# 24vacToIrRelayBoard-v1_2.net
KiCad netlist of a schematic drawn in EAGLE
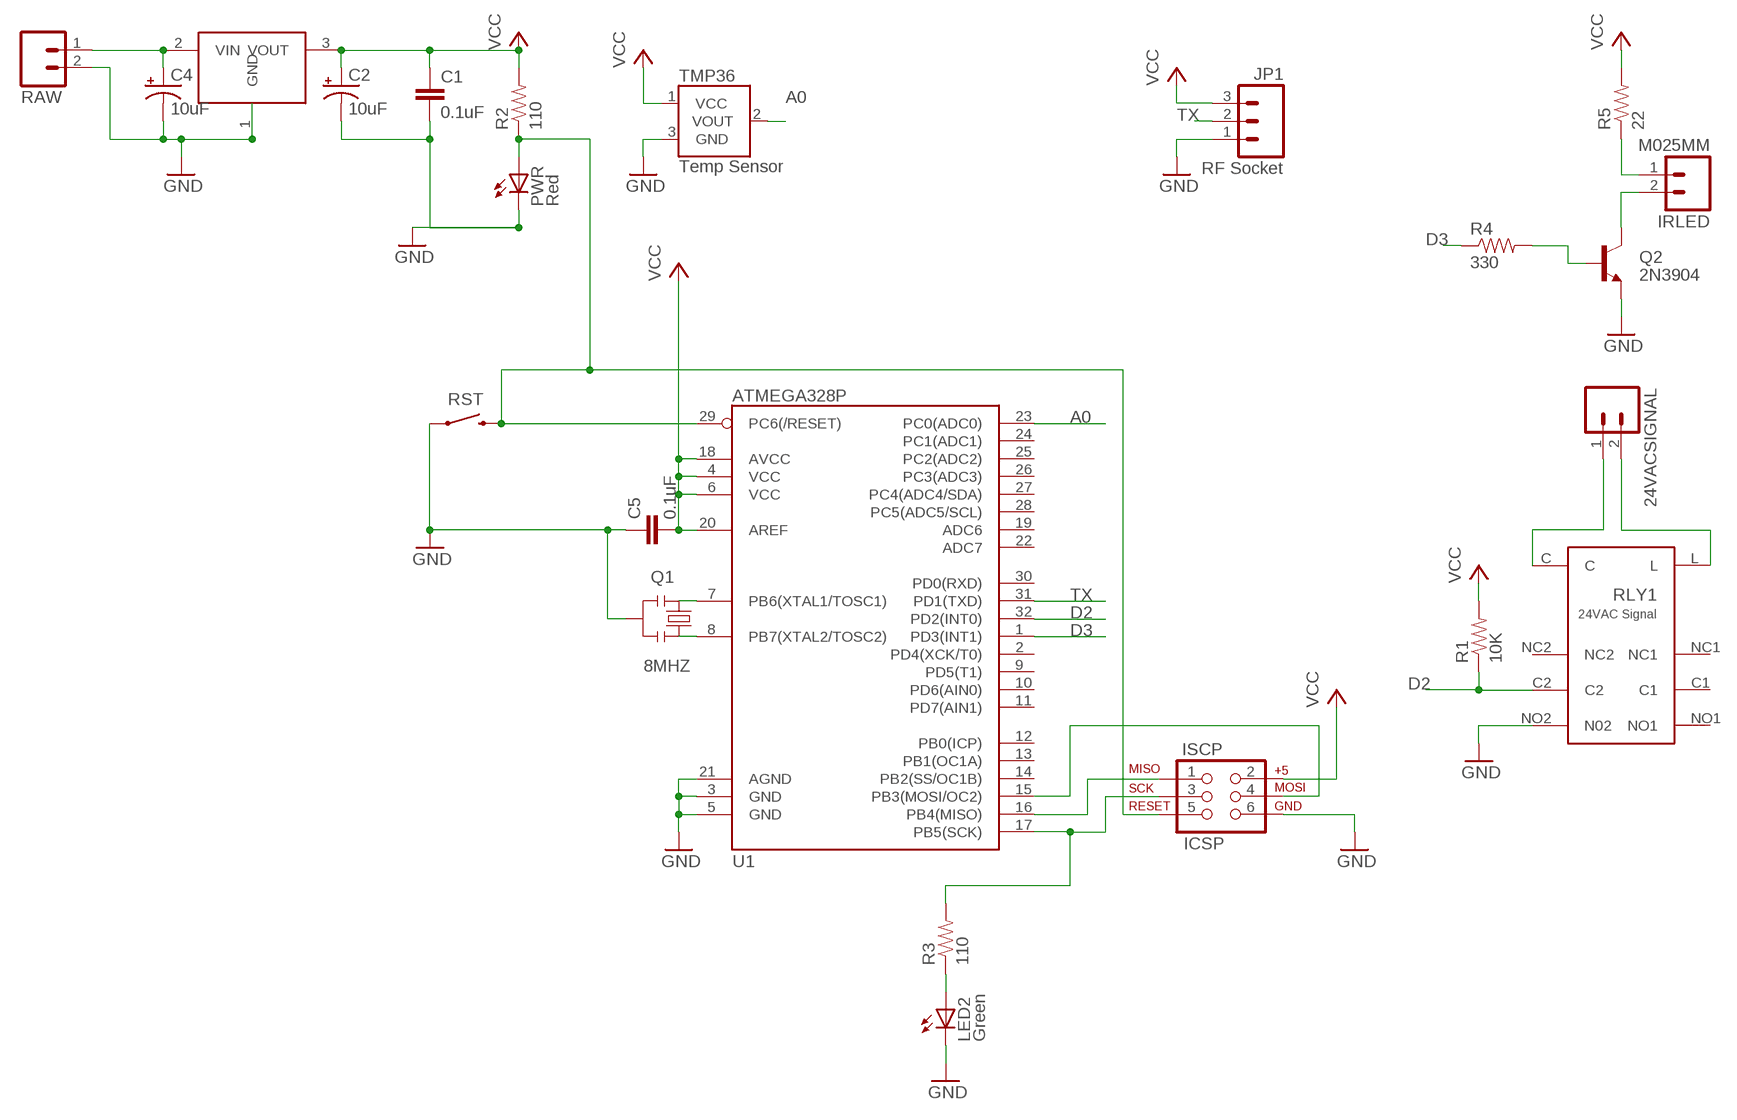
[diagram p0: schematic, sheet 1]

(export (version "E")
  (design (tool "Eeschema 10.0.6"))
  (components
    (comp (ref "24VACSIGNAL")
      (value "M025MM")
      (footprint "eagle-import:SCREWTERMINAL-5MM-2")
      (libsource (lib "eagle-import") (part "M025MM"))
    )
    (comp (ref "C1")
      (value "0.1uF")
      (footprint "eagle-import:0603-CAP")
      (libsource (lib "eagle-import") (part "0.1UF-25V-5%(0603)"))
    )
    (comp (ref "C2")
      (value "10uF")
      (footprint "eagle-import:EIA3216")
      (libsource (lib "eagle-import") (part "10UF-16V-10%(TANT)"))
    )
    (comp (ref "C4")
      (value "10uF")
      (footprint "eagle-import:EIA3216")
      (libsource (lib "eagle-import") (part "10UF-16V-10%(TANT)"))
    )
    (comp (ref "C5")
      (value "0.1uF")
      (footprint "eagle-import:0603-CAP")
      (libsource (lib "eagle-import") (part "0.1UF-25V-5%(0603)"))
    )
    (comp (ref "IRLED")
      (value "M025MM")
      (footprint "eagle-import:SCREWTERMINAL-5MM-2")
      (libsource (lib "eagle-import") (part "M025MM"))
    )
    (comp (ref "ISCP")
      (value "ICSP")
      (footprint "eagle-import:2X3-NS")
      (libsource (lib "eagle-import") (part "AVR_SPI_PRG_6NS"))
    )
    (comp (ref "JP1")
      (value "RF Socket")
      (footprint "eagle-import:1X03")
      (libsource (lib "eagle-import") (part "M03PTH"))
    )
    (comp (ref "LED2")
      (value "Green")
      (footprint "eagle-import:LED-0603")
      (libsource (lib "eagle-import") (part "LED0603"))
    )
    (comp (ref "PWR")
      (value "Red")
      (footprint "eagle-import:LED-0603")
      (libsource (lib "eagle-import") (part "LED0603"))
    )
    (comp (ref "Q1")
      (value "8MHZ")
      (footprint "eagle-import:RESONATOR-SMD")
      (libsource (lib "eagle-import") (part "RESONATOR8MHZ"))
    )
    (comp (ref "Q2")
      (value "2N3904")
      (footprint "eagle-import:SOT23-3")
      (libsource (lib "eagle-import") (part "TRANSISTOR_NPNSOT23-3"))
    )
    (comp (ref "R1")
      (value "10K")
      (footprint "eagle-import:0603-RES")
      (libsource (lib "eagle-import") (part "10KOHM1/10W1%(0603)0603"))
    )
    (comp (ref "R2")
      (value "110")
      (footprint "eagle-import:0603-RES")
      (libsource (lib "eagle-import") (part "10KOHM1/10W1%(0603)0603"))
    )
    (comp (ref "R3")
      (value "110")
      (footprint "eagle-import:0603-RES")
      (libsource (lib "eagle-import") (part "10KOHM1/10W1%(0603)0603"))
    )
    (comp (ref "R4")
      (value "330")
      (footprint "eagle-import:0603-RES")
      (libsource (lib "eagle-import") (part "10KOHM1/10W1%(0603)0603"))
    )
    (comp (ref "R5")
      (value "22")
      (footprint "eagle-import:0603-RES")
      (libsource (lib "eagle-import") (part "10KOHM1/10W1%(0603)0603"))
    )
    (comp (ref "RAW")
      (value "M025MM")
      (footprint "eagle-import:SCREWTERMINAL-5MM-2")
      (libsource (lib "eagle-import") (part "M025MM"))
    )
    (comp (ref "RLY1")
      (value "24VAC Signal")
      (footprint "eagle-import:976RELAY")
      (libsource (lib "eagle-import") (part "976XAX97H-24AA"))
    )
    (comp (ref "RST")
      (value "SWITCH-MOMENTARY-2PTH")
      (footprint "eagle-import:TACTILE-PTH")
      (libsource (lib "eagle-import") (part "SWITCH-MOMENTARY-2PTH"))
    )
    (comp (ref "TMP36")
      (value "Temp Sensor")
      (footprint "eagle-import:TO-92")
      (libsource (lib "eagle-import") (part "TMP36GT9"))
    )
    (comp (ref "U$1")
      (value "MCP1702")
      (footprint "eagle-import:TO92")
      (libsource (lib "eagle-import") (part "MCP1702"))
    )
    (comp (ref "U1")
      (value "ATMEGA328P")
      (footprint "eagle-import:TQFP32-08")
      (libsource (lib "eagle-import") (part "ATMEGA328_SMT"))
    )
  )
  (nets
    (net (code "1") (name "/A0") (class "Default")
      (node (ref "TMP36") (pin "2") (pinfunction "VOUT_2") (pintype "bidirectional"))
      (node (ref "U1") (pin "23") (pinfunction "PC0(ADC0)_23") (pintype "bidirectional"))
    )
    (net (code "2") (name "/D2") (class "Default")
      (node (ref "R1") (pin "1") (pinfunction "1_1") (pintype "passive"))
      (node (ref "RLY1") (pin "C2") (pinfunction "C2_C2") (pintype "bidirectional"))
      (node (ref "U1") (pin "32") (pinfunction "PD2(INT0)_32") (pintype "bidirectional"))
    )
    (net (code "3") (name "/D3") (class "Default")
      (node (ref "R4") (pin "1") (pinfunction "1_1") (pintype "passive"))
      (node (ref "U1") (pin "1") (pinfunction "PD3(INT1)_1") (pintype "bidirectional"))
    )
    (net (code "4") (name "/TX") (class "Default")
      (node (ref "JP1") (pin "2") (pinfunction "2_2") (pintype "passive"))
      (node (ref "U1") (pin "31") (pinfunction "PD1(TXD)_31") (pintype "bidirectional"))
    )
    (net (code "5") (name "GND") (class "Default")
      (node (ref "C1") (pin "2") (pinfunction "2_2") (pintype "passive"))
      (node (ref "C2") (pin "C") (pinfunction "-_C") (pintype "passive"))
      (node (ref "C4") (pin "C") (pinfunction "-_C") (pintype "passive"))
      (node (ref "C5") (pin "1") (pinfunction "1_1") (pintype "passive"))
      (node (ref "ISCP") (pin "6") (pinfunction "6_6") (pintype "passive"))
      (node (ref "JP1") (pin "1") (pinfunction "1_1") (pintype "passive"))
      (node (ref "LED2") (pin "C") (pinfunction "C_C") (pintype "passive"))
      (node (ref "PWR") (pin "C") (pinfunction "C_C") (pintype "passive"))
      (node (ref "Q1") (pin "2") (pinfunction "2_2") (pintype "passive"))
      (node (ref "Q2") (pin "2") (pinfunction "E_2") (pintype "passive"))
      (node (ref "RAW") (pin "2") (pinfunction "2_2") (pintype "passive"))
      (node (ref "RLY1") (pin "NO2") (pinfunction "N02_NO2") (pintype "bidirectional"))
      (node (ref "RST") (pin "1") (pinfunction "1_1") (pintype "passive"))
      (node (ref "TMP36") (pin "3") (pinfunction "GND_3") (pintype "bidirectional"))
      (node (ref "U$1") (pin "1") (pinfunction "GND_1") (pintype "bidirectional"))
      (node (ref "U1") (pin "21") (pinfunction "AGND_21") (pintype "bidirectional"))
      (node (ref "U1") (pin "3") (pinfunction "GND_3") (pintype "bidirectional"))
      (node (ref "U1") (pin "5") (pinfunction "GND_5") (pintype "bidirectional"))
    )
    (net (code "6") (name "Net-(24VACSIGNAL-Pad1)") (class "Default")
      (node (ref "24VACSIGNAL") (pin "1") (pinfunction "1_1") (pintype "passive"))
      (node (ref "RLY1") (pin "C") (pinfunction "C_C") (pintype "bidirectional"))
    )
    (net (code "7") (name "Net-(24VACSIGNAL-Pad2)") (class "Default")
      (node (ref "24VACSIGNAL") (pin "2") (pinfunction "2_2") (pintype "passive"))
      (node (ref "RLY1") (pin "L") (pinfunction "L_L") (pintype "bidirectional"))
    )
    (net (code "8") (name "Net-(C4-+)") (class "Default")
      (node (ref "C4") (pin "A") (pinfunction "+_A") (pintype "passive"))
      (node (ref "RAW") (pin "1") (pinfunction "1_1") (pintype "passive"))
      (node (ref "U$1") (pin "2") (pinfunction "VIN_2") (pintype "input"))
    )
    (net (code "9") (name "Net-(IRLED-Pad1)") (class "Default")
      (node (ref "IRLED") (pin "1") (pinfunction "1_1") (pintype "passive"))
      (node (ref "R5") (pin "1") (pinfunction "1_1") (pintype "passive"))
    )
    (net (code "10") (name "Net-(LED2-PadA)") (class "Default")
      (node (ref "LED2") (pin "A") (pinfunction "A_A") (pintype "passive"))
      (node (ref "R3") (pin "1") (pinfunction "1_1") (pintype "passive"))
    )
    (net (code "11") (name "Net-(Q2-B)") (class "Default")
      (node (ref "Q2") (pin "1") (pinfunction "B_1") (pintype "passive"))
      (node (ref "R4") (pin "2") (pinfunction "2_2") (pintype "passive"))
    )
    (net (code "12") (name "Net-(Q2-C)") (class "Default")
      (node (ref "IRLED") (pin "2") (pinfunction "2_2") (pintype "passive"))
      (node (ref "Q2") (pin "3") (pinfunction "C_3") (pintype "passive"))
    )
    (net (code "13") (name "Net-(RST-2)") (class "Default")
      (node (ref "ISCP") (pin "5") (pinfunction "5_5") (pintype "passive"))
      (node (ref "PWR") (pin "A") (pinfunction "A_A") (pintype "passive"))
      (node (ref "R2") (pin "1") (pinfunction "1_1") (pintype "passive"))
      (node (ref "RST") (pin "3") (pinfunction "2_3") (pintype "passive"))
      (node (ref "U1") (pin "29") (pinfunction "PC6(/RESET)_29") (pintype "bidirectional"))
    )
    (net (code "14") (name "Net-(U1-PB3(MOSI{slash}OC2))") (class "Default")
      (node (ref "ISCP") (pin "4") (pinfunction "4_4") (pintype "passive"))
      (node (ref "U1") (pin "15") (pinfunction "PB3(MOSI/OC2)_15") (pintype "bidirectional"))
    )
    (net (code "15") (name "Net-(U1-PB4(MISO))") (class "Default")
      (node (ref "ISCP") (pin "1") (pinfunction "1_1") (pintype "passive"))
      (node (ref "U1") (pin "16") (pinfunction "PB4(MISO)_16") (pintype "bidirectional"))
    )
    (net (code "16") (name "Net-(U1-PB5(SCK))") (class "Default")
      (node (ref "ISCP") (pin "3") (pinfunction "3_3") (pintype "passive"))
      (node (ref "R3") (pin "2") (pinfunction "2_2") (pintype "passive"))
      (node (ref "U1") (pin "17") (pinfunction "PB5(SCK)_17") (pintype "bidirectional"))
    )
    (net (code "17") (name "Net-(U1-PB6(XTAL1{slash}TOSC1))") (class "Default")
      (node (ref "Q1") (pin "1") (pinfunction "1_1") (pintype "passive"))
      (node (ref "U1") (pin "7") (pinfunction "PB6(XTAL1/TOSC1)_7") (pintype "bidirectional"))
    )
    (net (code "18") (name "Net-(U1-PB7(XTAL2{slash}TOSC2))") (class "Default")
      (node (ref "Q1") (pin "3") (pinfunction "3_3") (pintype "passive"))
      (node (ref "U1") (pin "8") (pinfunction "PB7(XTAL2/TOSC2)_8") (pintype "bidirectional"))
    )
    (net (code "19") (name "VCC") (class "Default")
      (node (ref "C1") (pin "1") (pinfunction "1_1") (pintype "passive"))
      (node (ref "C2") (pin "A") (pinfunction "+_A") (pintype "passive"))
      (node (ref "C5") (pin "2") (pinfunction "2_2") (pintype "passive"))
      (node (ref "ISCP") (pin "2") (pinfunction "2_2") (pintype "passive"))
      (node (ref "JP1") (pin "3") (pinfunction "3_3") (pintype "passive"))
      (node (ref "R1") (pin "2") (pinfunction "2_2") (pintype "passive"))
      (node (ref "R2") (pin "2") (pinfunction "2_2") (pintype "passive"))
      (node (ref "R5") (pin "2") (pinfunction "2_2") (pintype "passive"))
      (node (ref "TMP36") (pin "1") (pinfunction "VCC_1") (pintype "bidirectional"))
      (node (ref "U$1") (pin "3") (pinfunction "VOUT_3") (pintype "power_in"))
      (node (ref "U1") (pin "18") (pinfunction "AVCC_18") (pintype "bidirectional"))
      (node (ref "U1") (pin "20") (pinfunction "AREF_20") (pintype "bidirectional"))
      (node (ref "U1") (pin "4") (pinfunction "VCC_4") (pintype "bidirectional"))
      (node (ref "U1") (pin "6") (pinfunction "VCC_6") (pintype "bidirectional"))
    )
    (net (code "20") (name "unconnected-(RLY1-PadC1)") (class "Default")
      (node (ref "RLY1") (pin "C1") (pinfunction "C1_C1") (pintype "bidirectional"))
    )
    (net (code "21") (name "unconnected-(RLY1-PadNC1)") (class "Default")
      (node (ref "RLY1") (pin "NC1") (pinfunction "NC1_NC1") (pintype "bidirectional"))
    )
    (net (code "22") (name "unconnected-(RLY1-PadNC2)") (class "Default")
      (node (ref "RLY1") (pin "NC2") (pinfunction "NC2_NC2") (pintype "bidirectional"))
    )
    (net (code "23") (name "unconnected-(RLY1-PadNO1)") (class "Default")
      (node (ref "RLY1") (pin "NO1") (pinfunction "NO1_NO1") (pintype "bidirectional"))
    )
    (net (code "24") (name "unconnected-(U1-ADC6-Pad19)") (class "Default")
      (node (ref "U1") (pin "19") (pinfunction "ADC6_19") (pintype "bidirectional"))
    )
    (net (code "25") (name "unconnected-(U1-ADC7-Pad22)") (class "Default")
      (node (ref "U1") (pin "22") (pinfunction "ADC7_22") (pintype "bidirectional"))
    )
    (net (code "26") (name "unconnected-(U1-PB0(ICP)-Pad12)") (class "Default")
      (node (ref "U1") (pin "12") (pinfunction "PB0(ICP)_12") (pintype "bidirectional"))
    )
    (net (code "27") (name "unconnected-(U1-PB1(OC1A)-Pad13)") (class "Default")
      (node (ref "U1") (pin "13") (pinfunction "PB1(OC1A)_13") (pintype "bidirectional"))
    )
    (net (code "28") (name "unconnected-(U1-PB2(SS{slash}OC1B)-Pad14)") (class "Default")
      (node (ref "U1") (pin "14") (pinfunction "PB2(SS/OC1B)_14") (pintype "bidirectional"))
    )
    (net (code "29") (name "unconnected-(U1-PC1(ADC1)-Pad24)") (class "Default")
      (node (ref "U1") (pin "24") (pinfunction "PC1(ADC1)_24") (pintype "bidirectional"))
    )
    (net (code "30") (name "unconnected-(U1-PC2(ADC2)-Pad25)") (class "Default")
      (node (ref "U1") (pin "25") (pinfunction "PC2(ADC2)_25") (pintype "bidirectional"))
    )
    (net (code "31") (name "unconnected-(U1-PC3(ADC3)-Pad26)") (class "Default")
      (node (ref "U1") (pin "26") (pinfunction "PC3(ADC3)_26") (pintype "bidirectional"))
    )
    (net (code "32") (name "unconnected-(U1-PC4(ADC4{slash}SDA)-Pad27)") (class "Default")
      (node (ref "U1") (pin "27") (pinfunction "PC4(ADC4/SDA)_27") (pintype "bidirectional"))
    )
    (net (code "33") (name "unconnected-(U1-PC5(ADC5{slash}SCL)-Pad28)") (class "Default")
      (node (ref "U1") (pin "28") (pinfunction "PC5(ADC5/SCL)_28") (pintype "bidirectional"))
    )
    (net (code "34") (name "unconnected-(U1-PD0(RXD)-Pad30)") (class "Default")
      (node (ref "U1") (pin "30") (pinfunction "PD0(RXD)_30") (pintype "bidirectional"))
    )
    (net (code "35") (name "unconnected-(U1-PD4(XCK{slash}T0)-Pad2)") (class "Default")
      (node (ref "U1") (pin "2") (pinfunction "PD4(XCK/T0)_2") (pintype "bidirectional"))
    )
    (net (code "36") (name "unconnected-(U1-PD5(T1)-Pad9)") (class "Default")
      (node (ref "U1") (pin "9") (pinfunction "PD5(T1)_9") (pintype "bidirectional"))
    )
    (net (code "37") (name "unconnected-(U1-PD6(AIN0)-Pad10)") (class "Default")
      (node (ref "U1") (pin "10") (pinfunction "PD6(AIN0)_10") (pintype "bidirectional"))
    )
    (net (code "38") (name "unconnected-(U1-PD7(AIN1)-Pad11)") (class "Default")
      (node (ref "U1") (pin "11") (pinfunction "PD7(AIN1)_11") (pintype "bidirectional"))
    )
  )
)
